# budicLED.net
KiCad netlist of a schematic drawn in EAGLE
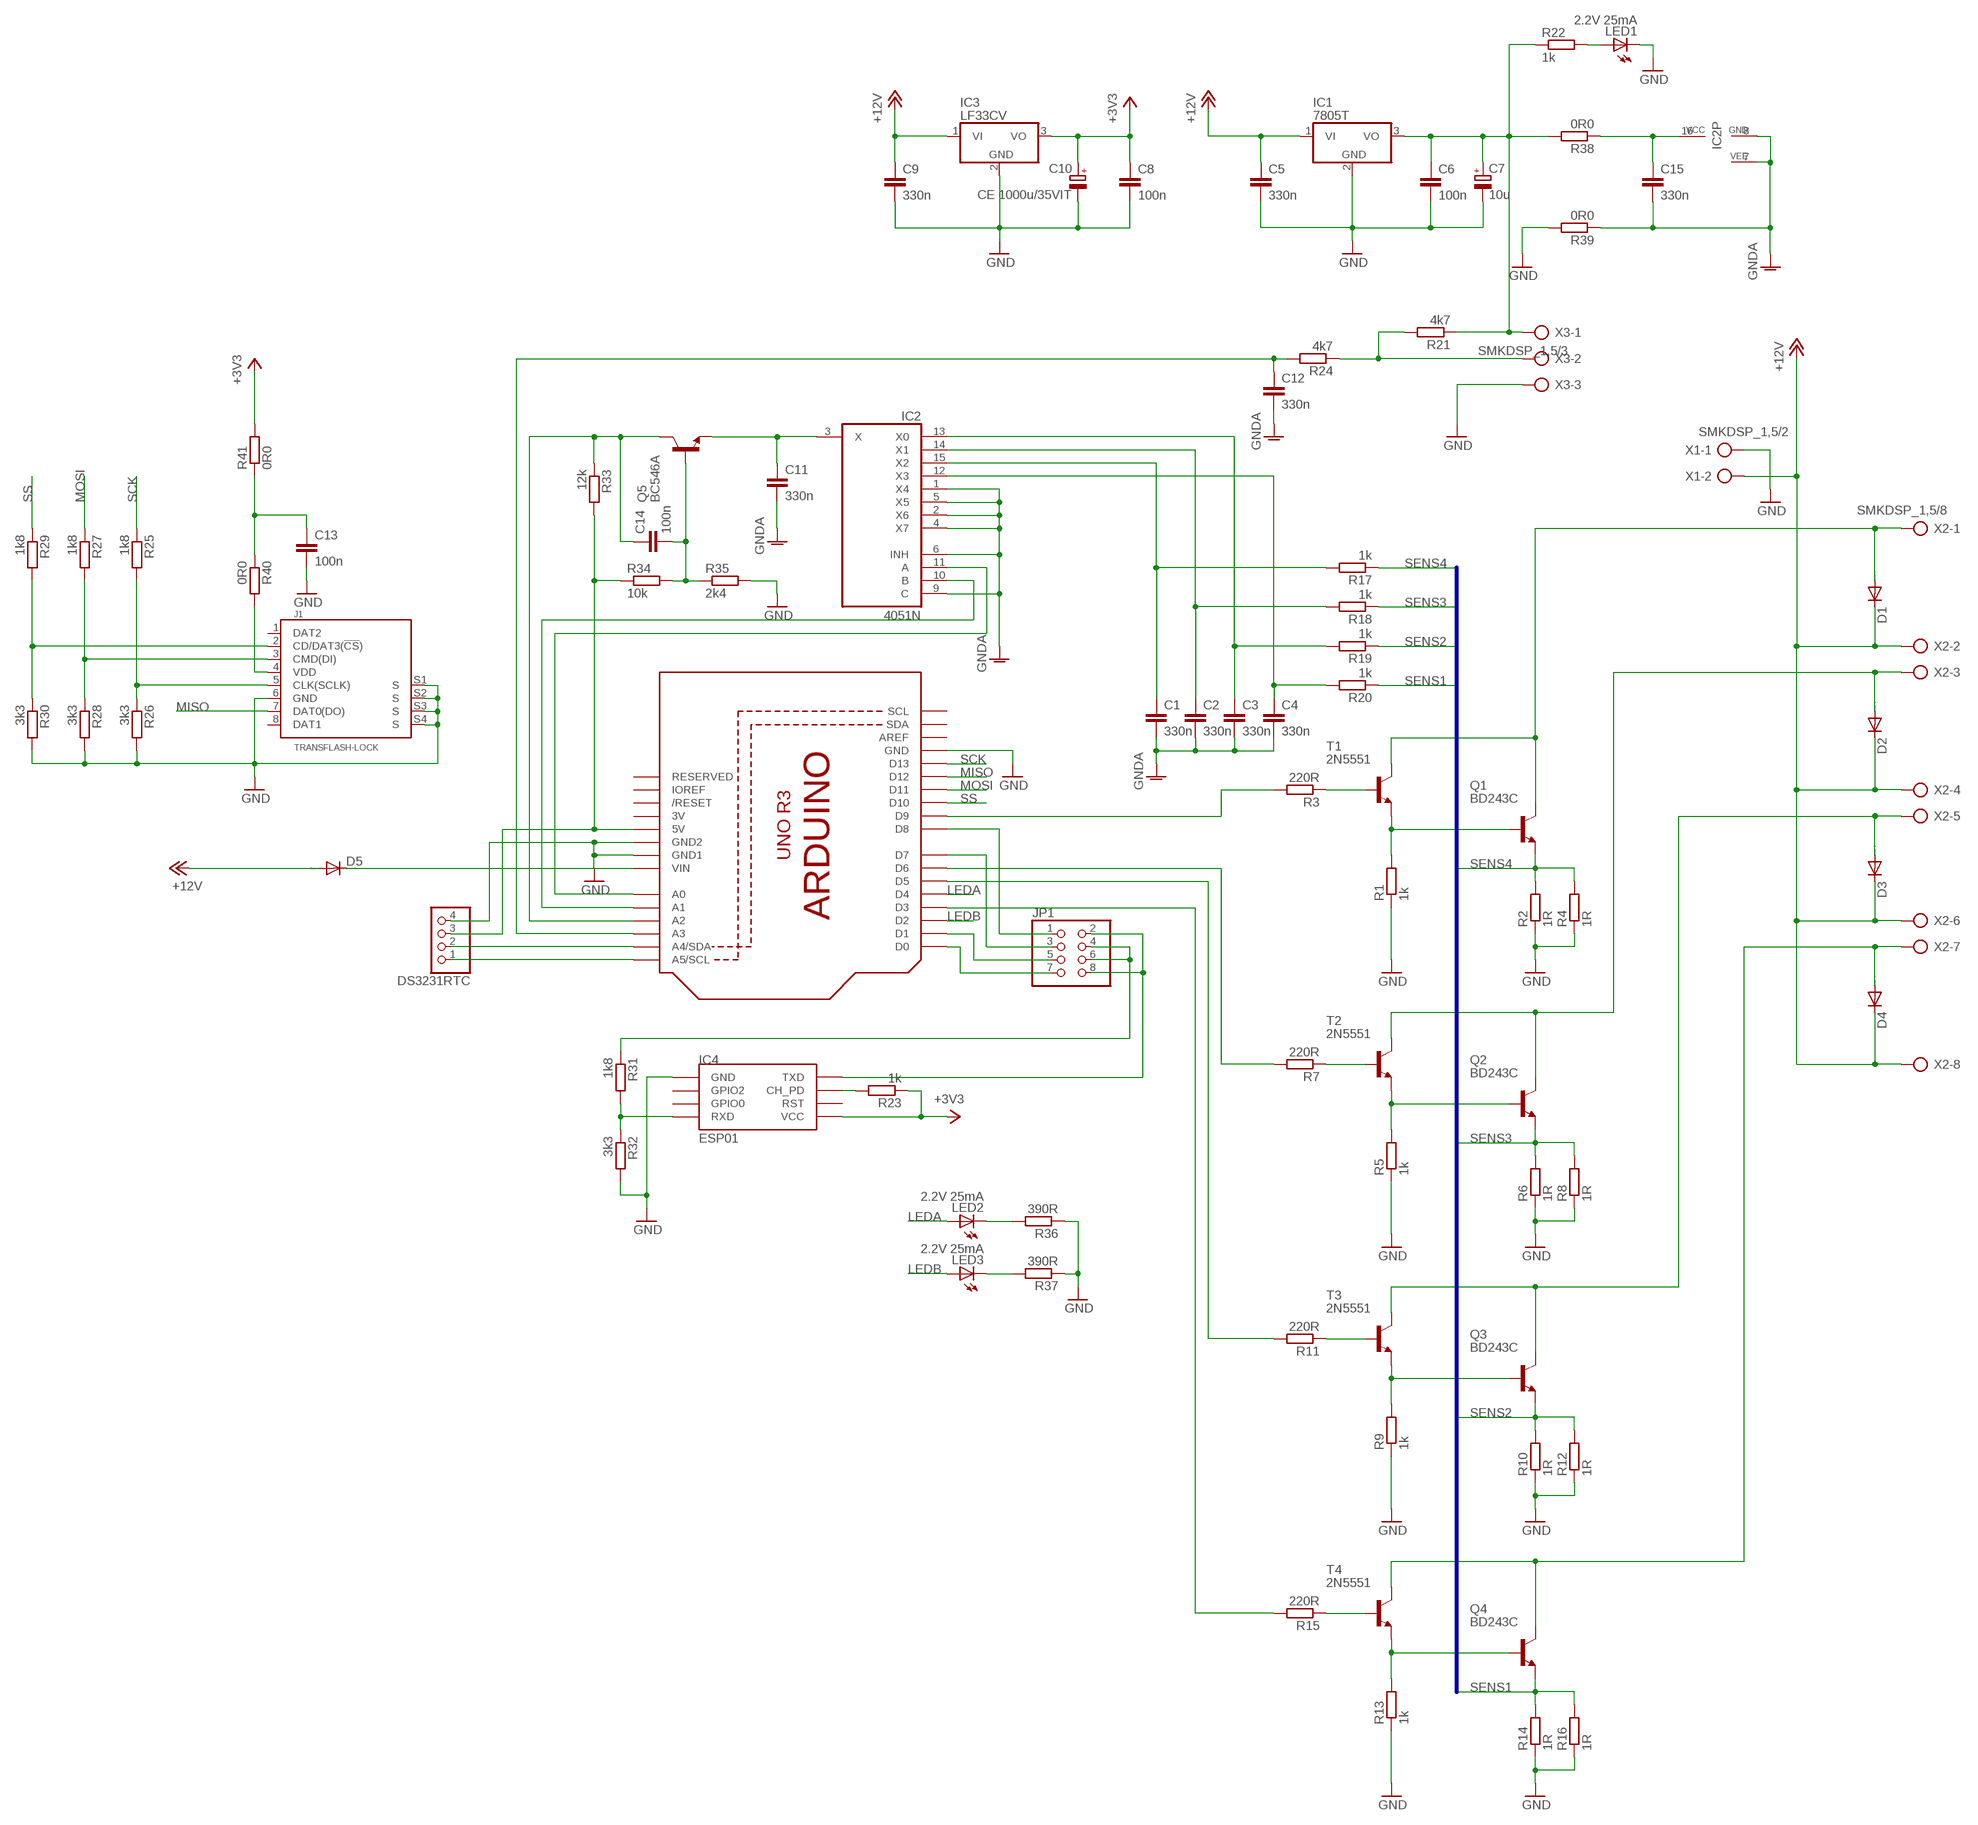
[diagram p0: schematic, sheet 1]

(export (version "E")
  (design (tool "Eeschema 10.0.6"))
  (components
    (comp (ref "C1")
      (value "330n")
      (footprint "eagle-import:C1206K")
      (libsource (lib "eagle-import") (part "C-EUC1206K"))
    )
    (comp (ref "C2")
      (value "330n")
      (footprint "eagle-import:C1206K")
      (libsource (lib "eagle-import") (part "C-EUC1206K"))
    )
    (comp (ref "C3")
      (value "330n")
      (footprint "eagle-import:C1206K")
      (libsource (lib "eagle-import") (part "C-EUC1206K"))
    )
    (comp (ref "C4")
      (value "330n")
      (footprint "eagle-import:C1206K")
      (libsource (lib "eagle-import") (part "C-EUC1206K"))
    )
    (comp (ref "C5")
      (value "330n")
      (footprint "eagle-import:C1206K")
      (libsource (lib "eagle-import") (part "C-EUC1206K"))
    )
    (comp (ref "C6")
      (value "100n")
      (footprint "eagle-import:C1206K")
      (libsource (lib "eagle-import") (part "C-EUC1206K"))
    )
    (comp (ref "C7")
      (value "10u")
      (footprint "eagle-import:E5-10,5")
      (libsource (lib "eagle-import") (part "CPOL-EUE5-10.5"))
    )
    (comp (ref "C8")
      (value "100n")
      (footprint "eagle-import:C1206K")
      (libsource (lib "eagle-import") (part "C-EUC1206K"))
    )
    (comp (ref "C9")
      (value "330n")
      (footprint "eagle-import:C1206K")
      (libsource (lib "eagle-import") (part "C-EUC1206K"))
    )
    (comp (ref "C10")
      (value "CE 1000u/35VIT")
      (footprint "eagle-import:E5-10,5")
      (libsource (lib "eagle-import") (part "CPOL-EUE5-10.5"))
    )
    (comp (ref "C11")
      (value "330n")
      (footprint "eagle-import:C1206K")
      (libsource (lib "eagle-import") (part "C-EUC1206K"))
    )
    (comp (ref "C12")
      (value "330n")
      (footprint "eagle-import:C1206K")
      (libsource (lib "eagle-import") (part "C-EUC1206K"))
    )
    (comp (ref "C13")
      (value "100n")
      (footprint "eagle-import:C1206K")
      (libsource (lib "eagle-import") (part "C-EUC1206K"))
    )
    (comp (ref "C14")
      (value "100n")
      (footprint "eagle-import:C1206K")
      (libsource (lib "eagle-import") (part "C-EUC1206K"))
    )
    (comp (ref "C15")
      (value "330n")
      (footprint "eagle-import:C1206K")
      (libsource (lib "eagle-import") (part "C-EUC1206K"))
    )
    (comp (ref "D1")
      (value "DIODE-DO201-15")
      (footprint "eagle-import:DO201-15")
      (libsource (lib "eagle-import") (part "DIODE-DO201-15"))
    )
    (comp (ref "D2")
      (value "DIODE-DO201-15")
      (footprint "eagle-import:DO201-15")
      (libsource (lib "eagle-import") (part "DIODE-DO201-15"))
    )
    (comp (ref "D3")
      (value "DIODE-DO201-15")
      (footprint "eagle-import:DO201-15")
      (libsource (lib "eagle-import") (part "DIODE-DO201-15"))
    )
    (comp (ref "D4")
      (value "DIODE-DO201-15")
      (footprint "eagle-import:DO201-15")
      (libsource (lib "eagle-import") (part "DIODE-DO201-15"))
    )
    (comp (ref "D5")
      (value "DIODE-MELF-MLL41")
      (footprint "eagle-import:MELF-MLL41")
      (libsource (lib "eagle-import") (part "DIODE-MELF-MLL41"))
    )
    (comp (ref "DS3231RTC")
      (value "PINHD-1X4")
      (footprint "eagle-import:1X04")
      (libsource (lib "eagle-import") (part "PINHD-1X4"))
    )
    (comp (ref "IC1")
      (value "7805T")
      (footprint "eagle-import:TO220H")
      (libsource (lib "eagle-import") (part "78T05"))
    )
    (comp (ref "IC2")
      (value "4051N")
      (footprint "eagle-import:DIL16")
      (libsource (lib "eagle-import") (part "4051N"))
    )
    (comp (ref "IC3")
      (value "LF33CV")
      (footprint "eagle-import:TO220H")
      (libsource (lib "eagle-import") (part "78T05"))
    )
    (comp (ref "IC4")
      (value "ESP01")
      (footprint "eagle-import:ESP01")
      (libsource (lib "eagle-import") (part "ESP01"))
    )
    (comp (ref "J1")
      (value "TRANSFLASH-LOCK")
      (footprint "eagle-import:TRANSFLASH-LOCK-SOCK")
      (libsource (lib "eagle-import") (part "TRANSFLASH-LOCK"))
    )
    (comp (ref "JP1")
      (value "PINHD-2X4")
      (footprint "eagle-import:2X04")
      (libsource (lib "eagle-import") (part "PINHD-2X4"))
    )
    (comp (ref "LED1")
      (value "2.2V 25mA")
      (footprint "eagle-import:LED3MM")
      (libsource (lib "eagle-import") (part "LED3MM"))
    )
    (comp (ref "LED2")
      (value "2.2V 25mA")
      (footprint "eagle-import:LED3MM")
      (libsource (lib "eagle-import") (part "LED3MM"))
    )
    (comp (ref "LED3")
      (value "2.2V 25mA")
      (footprint "eagle-import:LED3MM")
      (libsource (lib "eagle-import") (part "LED3MM"))
    )
    (comp (ref "Q1")
      (value "BD243C")
      (footprint "eagle-import:TO220")
      (libsource (lib "eagle-import") (part "-NPN-TO220"))
    )
    (comp (ref "Q2")
      (value "BD243C")
      (footprint "eagle-import:TO220")
      (libsource (lib "eagle-import") (part "-NPN-TO220"))
    )
    (comp (ref "Q3")
      (value "BD243C")
      (footprint "eagle-import:TO220")
      (libsource (lib "eagle-import") (part "-NPN-TO220"))
    )
    (comp (ref "Q4")
      (value "BD243C")
      (footprint "eagle-import:TO220")
      (libsource (lib "eagle-import") (part "-NPN-TO220"))
    )
    (comp (ref "Q5")
      (value "BC546A")
      (footprint "eagle-import:TO92-EBC")
      (libsource (lib "eagle-import") (part "BC546A"))
    )
    (comp (ref "R1")
      (value "1k")
      (footprint "eagle-import:0207_12")
      (libsource (lib "eagle-import") (part "R-EU_0207/12"))
    )
    (comp (ref "R2")
      (value "1R")
      (footprint "eagle-import:0411_15")
      (libsource (lib "eagle-import") (part "R-EU_0411/15"))
    )
    (comp (ref "R3")
      (value "220R")
      (footprint "eagle-import:0207_12")
      (libsource (lib "eagle-import") (part "R-EU_0207/12"))
    )
    (comp (ref "R4")
      (value "1R")
      (footprint "eagle-import:0411_15")
      (libsource (lib "eagle-import") (part "R-EU_0411/15"))
    )
    (comp (ref "R5")
      (value "1k")
      (footprint "eagle-import:0207_12")
      (libsource (lib "eagle-import") (part "R-EU_0207/12"))
    )
    (comp (ref "R6")
      (value "1R")
      (footprint "eagle-import:0411_15")
      (libsource (lib "eagle-import") (part "R-EU_0411/15"))
    )
    (comp (ref "R7")
      (value "220R")
      (footprint "eagle-import:0207_12")
      (libsource (lib "eagle-import") (part "R-EU_0207/12"))
    )
    (comp (ref "R8")
      (value "1R")
      (footprint "eagle-import:0411_15")
      (libsource (lib "eagle-import") (part "R-EU_0411/15"))
    )
    (comp (ref "R9")
      (value "1k")
      (footprint "eagle-import:0207_12")
      (libsource (lib "eagle-import") (part "R-EU_0207/12"))
    )
    (comp (ref "R10")
      (value "1R")
      (footprint "eagle-import:0411_15")
      (libsource (lib "eagle-import") (part "R-EU_0411/15"))
    )
    (comp (ref "R11")
      (value "220R")
      (footprint "eagle-import:0207_12")
      (libsource (lib "eagle-import") (part "R-EU_0207/12"))
    )
    (comp (ref "R12")
      (value "1R")
      (footprint "eagle-import:0411_15")
      (libsource (lib "eagle-import") (part "R-EU_0411/15"))
    )
    (comp (ref "R13")
      (value "1k")
      (footprint "eagle-import:0207_12")
      (libsource (lib "eagle-import") (part "R-EU_0207/12"))
    )
    (comp (ref "R14")
      (value "1R")
      (footprint "eagle-import:0411_15")
      (libsource (lib "eagle-import") (part "R-EU_0411/15"))
    )
    (comp (ref "R15")
      (value "220R")
      (footprint "eagle-import:0207_12")
      (libsource (lib "eagle-import") (part "R-EU_0207/12"))
    )
    (comp (ref "R16")
      (value "1R")
      (footprint "eagle-import:0411_15")
      (libsource (lib "eagle-import") (part "R-EU_0411/15"))
    )
    (comp (ref "R17")
      (value "1k")
      (footprint "eagle-import:R0805")
      (libsource (lib "eagle-import") (part "R-EU_R0805"))
    )
    (comp (ref "R18")
      (value "1k")
      (footprint "eagle-import:R0805")
      (libsource (lib "eagle-import") (part "R-EU_R0805"))
    )
    (comp (ref "R19")
      (value "1k")
      (footprint "eagle-import:R0805")
      (libsource (lib "eagle-import") (part "R-EU_R0805"))
    )
    (comp (ref "R20")
      (value "1k")
      (footprint "eagle-import:R0805")
      (libsource (lib "eagle-import") (part "R-EU_R0805"))
    )
    (comp (ref "R21")
      (value "4k7")
      (footprint "eagle-import:0207_12")
      (libsource (lib "eagle-import") (part "R-EU_0207/12"))
    )
    (comp (ref "R22")
      (value "1k")
      (footprint "eagle-import:R0805")
      (libsource (lib "eagle-import") (part "R-EU_R0805"))
    )
    (comp (ref "R23")
      (value "1k")
      (footprint "eagle-import:R0805")
      (libsource (lib "eagle-import") (part "R-EU_R0805"))
    )
    (comp (ref "R24")
      (value "4k7")
      (footprint "eagle-import:0207_15")
      (libsource (lib "eagle-import") (part "R-EU_0207/15"))
    )
    (comp (ref "R25")
      (value "1k8")
      (footprint "eagle-import:0207_12")
      (libsource (lib "eagle-import") (part "R-EU_0207/12"))
    )
    (comp (ref "R26")
      (value "3k3")
      (footprint "eagle-import:0207_12")
      (libsource (lib "eagle-import") (part "R-EU_0207/12"))
    )
    (comp (ref "R27")
      (value "1k8")
      (footprint "eagle-import:0207_12")
      (libsource (lib "eagle-import") (part "R-EU_0207/12"))
    )
    (comp (ref "R28")
      (value "3k3")
      (footprint "eagle-import:0207_12")
      (libsource (lib "eagle-import") (part "R-EU_0207/12"))
    )
    (comp (ref "R29")
      (value "1k8")
      (footprint "eagle-import:0207_12")
      (libsource (lib "eagle-import") (part "R-EU_0207/12"))
    )
    (comp (ref "R30")
      (value "3k3")
      (footprint "eagle-import:0207_12")
      (libsource (lib "eagle-import") (part "R-EU_0207/12"))
    )
    (comp (ref "R31")
      (value "1k8")
      (footprint "eagle-import:0207_12")
      (libsource (lib "eagle-import") (part "R-EU_0207/12"))
    )
    (comp (ref "R32")
      (value "3k3")
      (footprint "eagle-import:0207_12")
      (libsource (lib "eagle-import") (part "R-EU_0207/12"))
    )
    (comp (ref "R33")
      (value "12k")
      (footprint "eagle-import:0207_12")
      (libsource (lib "eagle-import") (part "R-EU_0207/12"))
    )
    (comp (ref "R34")
      (value "10k")
      (footprint "eagle-import:0207_12")
      (libsource (lib "eagle-import") (part "R-EU_0207/12"))
    )
    (comp (ref "R35")
      (value "2k4")
      (footprint "eagle-import:0207_12")
      (libsource (lib "eagle-import") (part "R-EU_0207/12"))
    )
    (comp (ref "R36")
      (value "390R")
      (footprint "eagle-import:0207_12")
      (libsource (lib "eagle-import") (part "R-EU_0207/12"))
    )
    (comp (ref "R37")
      (value "390R")
      (footprint "eagle-import:0207_12")
      (libsource (lib "eagle-import") (part "R-EU_0207/12"))
    )
    (comp (ref "R38")
      (value "0R0")
      (footprint "eagle-import:0207_15")
      (libsource (lib "eagle-import") (part "R-EU_0207/15"))
    )
    (comp (ref "R39")
      (value "0R0")
      (footprint "eagle-import:0207_12")
      (libsource (lib "eagle-import") (part "R-EU_0207/12"))
    )
    (comp (ref "R40")
      (value "0R0")
      (footprint "eagle-import:0207_12")
      (libsource (lib "eagle-import") (part "R-EU_0207/12"))
    )
    (comp (ref "R41")
      (value "0R0")
      (footprint "eagle-import:0207_12")
      (libsource (lib "eagle-import") (part "R-EU_0207/12"))
    )
    (comp (ref "T1")
      (value "2N5551")
      (footprint "eagle-import:TO92-CBE")
      (libsource (lib "eagle-import") (part "-NPN-TO92-CBE2N5551"))
    )
    (comp (ref "T2")
      (value "2N5551")
      (footprint "eagle-import:TO92-CBE")
      (libsource (lib "eagle-import") (part "-NPN-TO92-CBE2N5551"))
    )
    (comp (ref "T3")
      (value "2N5551")
      (footprint "eagle-import:TO92-CBE")
      (libsource (lib "eagle-import") (part "-NPN-TO92-CBE2N5551"))
    )
    (comp (ref "T4")
      (value "2N5551")
      (footprint "eagle-import:TO92-CBE")
      (libsource (lib "eagle-import") (part "-NPN-TO92-CBE2N5551"))
    )
    (comp (ref "U1")
      (value "ARDUINOR3-DIMENSION")
      (footprint "eagle-import:ARDUINOR3")
      (libsource (lib "eagle-import") (part "ARDUINOR3-DIMENSION"))
    )
    (comp (ref "X1")
      (value "SMKDSP_1,5/2")
      (footprint "eagle-import:SMKDSP_1,5_2")
      (fields (field (name "MF") "FARNELL") (field (name "MPN") "1733570"))
      (libsource (lib "eagle-import") (part "SMKDSP_1,5/2"))
    )
    (comp (ref "X2")
      (value "SMKDSP_1,5/8")
      (footprint "eagle-import:SMKDSP_1,5_8")
      (fields (field (name "MF") "FARNELL") (field (name "MPN") "1733635"))
      (libsource (lib "eagle-import") (part "SMKDSP_1,5/8"))
    )
    (comp (ref "X3")
      (value "SMKDSP_1,5/3")
      (footprint "eagle-import:SMKDSP_1,5_3")
      (fields (field (name "MF") "FARNELL") (field (name "MPN") "1733583"))
      (libsource (lib "eagle-import") (part "SMKDSP_1,5/3"))
    )
  )
  (nets
    (net (code "1") (name "+3V3") (class "Default")
      (node (ref "C10") (pin "+") (pinfunction "+_+") (pintype "passive"))
      (node (ref "C8") (pin "1") (pinfunction "1_1") (pintype "passive"))
      (node (ref "IC3") (pin "3") (pinfunction "VO_3") (pintype "passive"))
      (node (ref "IC4") (pin "VCC") (pinfunction "VCC_VCC") (pintype "bidirectional"))
      (node (ref "R23") (pin "1") (pinfunction "1_1") (pintype "passive"))
      (node (ref "R41") (pin "2") (pinfunction "2_2") (pintype "passive"))
    )
    (net (code "2") (name "+12V") (class "Default")
      (node (ref "C5") (pin "1") (pinfunction "1_1") (pintype "passive"))
      (node (ref "C9") (pin "1") (pinfunction "1_1") (pintype "passive"))
      (node (ref "D1") (pin "C") (pinfunction "C_C") (pintype "passive"))
      (node (ref "D2") (pin "C") (pinfunction "C_C") (pintype "passive"))
      (node (ref "D3") (pin "C") (pinfunction "C_C") (pintype "passive"))
      (node (ref "D4") (pin "C") (pinfunction "C_C") (pintype "passive"))
      (node (ref "D5") (pin "A") (pinfunction "A_A") (pintype "passive"))
      (node (ref "IC1") (pin "1") (pinfunction "VI_1") (pintype "input"))
      (node (ref "IC3") (pin "1") (pinfunction "VI_1") (pintype "input"))
      (node (ref "X1") (pin "2") (pinfunction "KL_2") (pintype "passive"))
      (node (ref "X2") (pin "2") (pinfunction "KL_2") (pintype "passive"))
      (node (ref "X2") (pin "4") (pinfunction "KL_4") (pintype "passive"))
      (node (ref "X2") (pin "6") (pinfunction "KL_6") (pintype "passive"))
      (node (ref "X2") (pin "8") (pinfunction "KL_8") (pintype "passive"))
    )
    (net (code "3") (name "/3V") (class "Default")
      (node (ref "U1") (pin "3V") (pinfunction "3V_3V") (pintype "power_in"))
    )
    (net (code "4") (name "/LEDA") (class "Default")
      (node (ref "LED2") (pin "A") (pinfunction "A_A") (pintype "passive"))
      (node (ref "U1") (pin "D4") (pinfunction "D4_D4") (pintype "bidirectional"))
    )
    (net (code "5") (name "/LEDB") (class "Default")
      (node (ref "LED3") (pin "A") (pinfunction "A_A") (pintype "passive"))
      (node (ref "U1") (pin "D2") (pinfunction "D2_D2") (pintype "bidirectional"))
    )
    (net (code "6") (name "/MISO") (class "Default")
      (node (ref "J1") (pin "7") (pinfunction "DAT0(DO)_7") (pintype "bidirectional"))
      (node (ref "U1") (pin "D12") (pinfunction "D12_D12") (pintype "bidirectional"))
    )
    (net (code "7") (name "/MOSI") (class "Default")
      (node (ref "R27") (pin "1") (pinfunction "1_1") (pintype "passive"))
      (node (ref "U1") (pin "D11") (pinfunction "D11_D11") (pintype "bidirectional"))
    )
    (net (code "8") (name "/SCK") (class "Default")
      (node (ref "R25") (pin "1") (pinfunction "1_1") (pintype "passive"))
      (node (ref "U1") (pin "D13") (pinfunction "D13_D13") (pintype "bidirectional"))
    )
    (net (code "9") (name "/SENS1") (class "Default")
      (node (ref "Q4") (pin "3") (pinfunction "E_3") (pintype "passive"))
      (node (ref "R14") (pin "2") (pinfunction "2_2") (pintype "passive"))
      (node (ref "R16") (pin "2") (pinfunction "2_2") (pintype "passive"))
      (node (ref "R20") (pin "1") (pinfunction "1_1") (pintype "passive"))
    )
    (net (code "10") (name "/SENS2") (class "Default")
      (node (ref "Q3") (pin "3") (pinfunction "E_3") (pintype "passive"))
      (node (ref "R10") (pin "2") (pinfunction "2_2") (pintype "passive"))
      (node (ref "R12") (pin "2") (pinfunction "2_2") (pintype "passive"))
      (node (ref "R19") (pin "1") (pinfunction "1_1") (pintype "passive"))
    )
    (net (code "11") (name "/SENS3") (class "Default")
      (node (ref "Q2") (pin "3") (pinfunction "E_3") (pintype "passive"))
      (node (ref "R18") (pin "1") (pinfunction "1_1") (pintype "passive"))
      (node (ref "R6") (pin "2") (pinfunction "2_2") (pintype "passive"))
      (node (ref "R8") (pin "2") (pinfunction "2_2") (pintype "passive"))
    )
    (net (code "12") (name "/SENS4") (class "Default")
      (node (ref "Q1") (pin "3") (pinfunction "E_3") (pintype "passive"))
      (node (ref "R17") (pin "1") (pinfunction "1_1") (pintype "passive"))
      (node (ref "R2") (pin "2") (pinfunction "2_2") (pintype "passive"))
      (node (ref "R4") (pin "2") (pinfunction "2_2") (pintype "passive"))
    )
    (net (code "13") (name "/SS") (class "Default")
      (node (ref "R29") (pin "1") (pinfunction "1_1") (pintype "passive"))
      (node (ref "U1") (pin "D10") (pinfunction "D10_D10") (pintype "bidirectional"))
    )
    (net (code "14") (name "GND") (class "Default")
      (node (ref "C10") (pin "-") (pinfunction "-_-") (pintype "passive"))
      (node (ref "C13") (pin "2") (pinfunction "2_2") (pintype "passive"))
      (node (ref "C5") (pin "2") (pinfunction "2_2") (pintype "passive"))
      (node (ref "C6") (pin "2") (pinfunction "2_2") (pintype "passive"))
      (node (ref "C7") (pin "-") (pinfunction "-_-") (pintype "passive"))
      (node (ref "C8") (pin "2") (pinfunction "2_2") (pintype "passive"))
      (node (ref "C9") (pin "2") (pinfunction "2_2") (pintype "passive"))
      (node (ref "DS3231RTC") (pin "4") (pinfunction "4_4") (pintype "passive"))
      (node (ref "IC1") (pin "2") (pinfunction "GND_2") (pintype "passive"))
      (node (ref "IC3") (pin "2") (pinfunction "GND_2") (pintype "passive"))
      (node (ref "IC4") (pin "GND") (pinfunction "GND_GND") (pintype "bidirectional"))
      (node (ref "J1") (pin "6") (pinfunction "GND_6") (pintype "power_in"))
      (node (ref "J1") (pin "S1") (pinfunction "S_S1") (pintype "passive"))
      (node (ref "J1") (pin "S2") (pinfunction "S_S2") (pintype "passive"))
      (node (ref "J1") (pin "S3") (pinfunction "S_S3") (pintype "passive"))
      (node (ref "J1") (pin "S4") (pinfunction "S_S4") (pintype "passive"))
      (node (ref "LED1") (pin "K") (pinfunction "C_K") (pintype "passive"))
      (node (ref "R1") (pin "1") (pinfunction "1_1") (pintype "passive"))
      (node (ref "R10") (pin "1") (pinfunction "1_1") (pintype "passive"))
      (node (ref "R12") (pin "1") (pinfunction "1_1") (pintype "passive"))
      (node (ref "R13") (pin "1") (pinfunction "1_1") (pintype "passive"))
      (node (ref "R14") (pin "1") (pinfunction "1_1") (pintype "passive"))
      (node (ref "R16") (pin "1") (pinfunction "1_1") (pintype "passive"))
      (node (ref "R2") (pin "1") (pinfunction "1_1") (pintype "passive"))
      (node (ref "R26") (pin "2") (pinfunction "2_2") (pintype "passive"))
      (node (ref "R28") (pin "2") (pinfunction "2_2") (pintype "passive"))
      (node (ref "R30") (pin "2") (pinfunction "2_2") (pintype "passive"))
      (node (ref "R32") (pin "2") (pinfunction "2_2") (pintype "passive"))
      (node (ref "R35") (pin "2") (pinfunction "2_2") (pintype "passive"))
      (node (ref "R36") (pin "1") (pinfunction "1_1") (pintype "passive"))
      (node (ref "R37") (pin "1") (pinfunction "1_1") (pintype "passive"))
      (node (ref "R39") (pin "2") (pinfunction "2_2") (pintype "passive"))
      (node (ref "R4") (pin "1") (pinfunction "1_1") (pintype "passive"))
      (node (ref "R5") (pin "1") (pinfunction "1_1") (pintype "passive"))
      (node (ref "R6") (pin "1") (pinfunction "1_1") (pintype "passive"))
      (node (ref "R8") (pin "1") (pinfunction "1_1") (pintype "passive"))
      (node (ref "R9") (pin "1") (pinfunction "1_1") (pintype "passive"))
      (node (ref "U1") (pin "GND") (pinfunction "GND_GND") (pintype "power_in"))
      (node (ref "U1") (pin "GND1") (pinfunction "GND1_GND1") (pintype "power_in"))
      (node (ref "U1") (pin "GND2") (pinfunction "GND2_GND2") (pintype "power_in"))
      (node (ref "X1") (pin "1") (pinfunction "KL_1") (pintype "passive"))
      (node (ref "X3") (pin "3") (pinfunction "KL_3") (pintype "passive"))
    )
    (net (code "15") (name "GNDA") (class "Default")
      (node (ref "C1") (pin "2") (pinfunction "2_2") (pintype "passive"))
      (node (ref "C11") (pin "2") (pinfunction "2_2") (pintype "passive"))
      (node (ref "C12") (pin "2") (pinfunction "2_2") (pintype "passive"))
      (node (ref "C15") (pin "2") (pinfunction "2_2") (pintype "passive"))
      (node (ref "C2") (pin "2") (pinfunction "2_2") (pintype "passive"))
      (node (ref "C3") (pin "2") (pinfunction "2_2") (pintype "passive"))
      (node (ref "C4") (pin "2") (pinfunction "2_2") (pintype "passive"))
      (node (ref "IC2") (pin "1") (pinfunction "X4_1") (pintype "bidirectional"))
      (node (ref "IC2") (pin "2") (pinfunction "X6_2") (pintype "bidirectional"))
      (node (ref "IC2") (pin "4") (pinfunction "X7_4") (pintype "bidirectional"))
      (node (ref "IC2") (pin "5") (pinfunction "X5_5") (pintype "bidirectional"))
      (node (ref "IC2") (pin "6") (pinfunction "INH_6") (pintype "input"))
      (node (ref "IC2") (pin "7") (pinfunction "VEE_7") (pintype "power_in"))
      (node (ref "IC2") (pin "8") (pinfunction "GND_8") (pintype "power_in"))
      (node (ref "IC2") (pin "9") (pinfunction "C_9") (pintype "input"))
      (node (ref "R39") (pin "1") (pinfunction "1_1") (pintype "passive"))
    )
    (net (code "16") (name "Net-(C12-Pad1)") (class "Default")
      (node (ref "C12") (pin "1") (pinfunction "1_1") (pintype "passive"))
      (node (ref "R24") (pin "2") (pinfunction "2_2") (pintype "passive"))
      (node (ref "U1") (pin "A3") (pinfunction "A3_A3") (pintype "bidirectional"))
    )
    (net (code "17") (name "Net-(C13-Pad1)") (class "Default")
      (node (ref "C13") (pin "1") (pinfunction "1_1") (pintype "passive"))
      (node (ref "R40") (pin "1") (pinfunction "1_1") (pintype "passive"))
      (node (ref "R41") (pin "1") (pinfunction "1_1") (pintype "passive"))
    )
    (net (code "18") (name "Net-(C14-Pad1)") (class "Default")
      (node (ref "C14") (pin "1") (pinfunction "1_1") (pintype "passive"))
      (node (ref "Q5") (pin "C") (pinfunction "C_C") (pintype "passive"))
      (node (ref "R33") (pin "1") (pinfunction "1_1") (pintype "passive"))
      (node (ref "U1") (pin "A2") (pinfunction "A2_A2") (pintype "bidirectional"))
    )
    (net (code "19") (name "Net-(C14-Pad2)") (class "Default")
      (node (ref "C14") (pin "2") (pinfunction "2_2") (pintype "passive"))
      (node (ref "Q5") (pin "B") (pinfunction "B_B") (pintype "passive"))
      (node (ref "R34") (pin "2") (pinfunction "2_2") (pintype "passive"))
      (node (ref "R35") (pin "1") (pinfunction "1_1") (pintype "passive"))
    )
    (net (code "20") (name "Net-(D5-PadC)") (class "Default")
      (node (ref "D5") (pin "C") (pinfunction "C_C") (pintype "passive"))
      (node (ref "U1") (pin "VIN") (pinfunction "VIN_VIN") (pintype "power_in"))
    )
    (net (code "21") (name "Net-(DS3231RTC-Pad3)") (class "Default")
      (node (ref "DS3231RTC") (pin "3") (pinfunction "3_3") (pintype "passive"))
      (node (ref "R33") (pin "2") (pinfunction "2_2") (pintype "passive"))
      (node (ref "R34") (pin "1") (pinfunction "1_1") (pintype "passive"))
      (node (ref "U1") (pin "5V") (pinfunction "5V_5V") (pintype "power_in"))
    )
    (net (code "22") (name "Net-(IC1-VO)") (class "Default")
      (node (ref "C6") (pin "1") (pinfunction "1_1") (pintype "passive"))
      (node (ref "C7") (pin "+") (pinfunction "+_+") (pintype "passive"))
      (node (ref "IC1") (pin "3") (pinfunction "VO_3") (pintype "passive"))
      (node (ref "R21") (pin "1") (pinfunction "1_1") (pintype "passive"))
      (node (ref "R22") (pin "1") (pinfunction "1_1") (pintype "passive"))
      (node (ref "R38") (pin "2") (pinfunction "2_2") (pintype "passive"))
      (node (ref "X3") (pin "1") (pinfunction "KL_1") (pintype "passive"))
    )
    (net (code "23") (name "Net-(IC2A-A)") (class "Default")
      (node (ref "IC2") (pin "11") (pinfunction "A_11") (pintype "input"))
      (node (ref "U1") (pin "A0") (pinfunction "A0_A0") (pintype "bidirectional"))
    )
    (net (code "24") (name "Net-(IC2A-B)") (class "Default")
      (node (ref "IC2") (pin "10") (pinfunction "B_10") (pintype "input"))
      (node (ref "U1") (pin "A1") (pinfunction "A1_A1") (pintype "bidirectional"))
    )
    (net (code "25") (name "Net-(IC2A-X)") (class "Default")
      (node (ref "C11") (pin "1") (pinfunction "1_1") (pintype "passive"))
      (node (ref "IC2") (pin "3") (pinfunction "X_3") (pintype "bidirectional"))
      (node (ref "Q5") (pin "E") (pinfunction "E_E") (pintype "passive"))
    )
    (net (code "26") (name "Net-(IC2A-X0)") (class "Default")
      (node (ref "C3") (pin "1") (pinfunction "1_1") (pintype "passive"))
      (node (ref "IC2") (pin "13") (pinfunction "X0_13") (pintype "bidirectional"))
      (node (ref "R19") (pin "2") (pinfunction "2_2") (pintype "passive"))
    )
    (net (code "27") (name "Net-(IC2A-X1)") (class "Default")
      (node (ref "C2") (pin "1") (pinfunction "1_1") (pintype "passive"))
      (node (ref "IC2") (pin "14") (pinfunction "X1_14") (pintype "bidirectional"))
      (node (ref "R18") (pin "2") (pinfunction "2_2") (pintype "passive"))
    )
    (net (code "28") (name "Net-(IC2A-X2)") (class "Default")
      (node (ref "C1") (pin "1") (pinfunction "1_1") (pintype "passive"))
      (node (ref "IC2") (pin "15") (pinfunction "X2_15") (pintype "bidirectional"))
      (node (ref "R17") (pin "2") (pinfunction "2_2") (pintype "passive"))
    )
    (net (code "29") (name "Net-(IC2A-X3)") (class "Default")
      (node (ref "C4") (pin "1") (pinfunction "1_1") (pintype "passive"))
      (node (ref "IC2") (pin "12") (pinfunction "X3_12") (pintype "bidirectional"))
      (node (ref "R20") (pin "2") (pinfunction "2_2") (pintype "passive"))
    )
    (net (code "30") (name "Net-(IC2B-VCC)") (class "Default")
      (node (ref "C15") (pin "1") (pinfunction "1_1") (pintype "passive"))
      (node (ref "IC2") (pin "16") (pinfunction "VCC_16") (pintype "power_in"))
      (node (ref "R38") (pin "1") (pinfunction "1_1") (pintype "passive"))
    )
    (net (code "31") (name "Net-(IC4-PadCH_PD)") (class "Default")
      (node (ref "IC4") (pin "CH_PD") (pinfunction "CH_PD_CH_PD") (pintype "bidirectional"))
      (node (ref "R23") (pin "2") (pinfunction "2_2") (pintype "passive"))
    )
    (net (code "32") (name "Net-(IC4-RXD)") (class "Default")
      (node (ref "IC4") (pin "RX") (pinfunction "RXD_RX") (pintype "bidirectional"))
      (node (ref "R31") (pin "2") (pinfunction "2_2") (pintype "passive"))
      (node (ref "R32") (pin "1") (pinfunction "1_1") (pintype "passive"))
    )
    (net (code "33") (name "Net-(IC4-TXD)") (class "Default")
      (node (ref "IC4") (pin "TX") (pinfunction "TXD_TX") (pintype "bidirectional"))
      (node (ref "JP1") (pin "2") (pinfunction "2_2") (pintype "passive"))
      (node (ref "JP1") (pin "8") (pinfunction "8_8") (pintype "passive"))
    )
    (net (code "34") (name "Net-(J1-CD{slash}DAT3(~{CS}))") (class "Default")
      (node (ref "J1") (pin "2") (pinfunction "CD/DAT3(~{CS})_2") (pintype "bidirectional"))
      (node (ref "R29") (pin "2") (pinfunction "2_2") (pintype "passive"))
      (node (ref "R30") (pin "1") (pinfunction "1_1") (pintype "passive"))
    )
    (net (code "35") (name "Net-(J1-CLK(SCLK))") (class "Default")
      (node (ref "J1") (pin "5") (pinfunction "CLK(SCLK)_5") (pintype "bidirectional"))
      (node (ref "R25") (pin "2") (pinfunction "2_2") (pintype "passive"))
      (node (ref "R26") (pin "1") (pinfunction "1_1") (pintype "passive"))
    )
    (net (code "36") (name "Net-(J1-CMD(DI))") (class "Default")
      (node (ref "J1") (pin "3") (pinfunction "CMD(DI)_3") (pintype "bidirectional"))
      (node (ref "R27") (pin "2") (pinfunction "2_2") (pintype "passive"))
      (node (ref "R28") (pin "1") (pinfunction "1_1") (pintype "passive"))
    )
    (net (code "37") (name "Net-(J1-VDD)") (class "Default")
      (node (ref "J1") (pin "4") (pinfunction "VDD_4") (pintype "power_in"))
      (node (ref "R40") (pin "2") (pinfunction "2_2") (pintype "passive"))
    )
    (net (code "38") (name "Net-(JP1-Pad1)") (class "Default")
      (node (ref "JP1") (pin "1") (pinfunction "1_1") (pintype "passive"))
      (node (ref "U1") (pin "D8") (pinfunction "D8_D8") (pintype "bidirectional"))
    )
    (net (code "39") (name "Net-(JP1-Pad3)") (class "Default")
      (node (ref "JP1") (pin "3") (pinfunction "3_3") (pintype "passive"))
      (node (ref "U1") (pin "D7") (pinfunction "D7_D7") (pintype "bidirectional"))
    )
    (net (code "40") (name "Net-(JP1-Pad4)") (class "Default")
      (node (ref "JP1") (pin "4") (pinfunction "4_4") (pintype "passive"))
      (node (ref "JP1") (pin "6") (pinfunction "6_6") (pintype "passive"))
      (node (ref "R31") (pin "1") (pinfunction "1_1") (pintype "passive"))
    )
    (net (code "41") (name "Net-(JP1-Pad5)") (class "Default")
      (node (ref "JP1") (pin "5") (pinfunction "5_5") (pintype "passive"))
      (node (ref "U1") (pin "D1") (pinfunction "D1_D1") (pintype "bidirectional"))
    )
    (net (code "42") (name "Net-(JP1-Pad7)") (class "Default")
      (node (ref "JP1") (pin "7") (pinfunction "7_7") (pintype "passive"))
      (node (ref "U1") (pin "D0") (pinfunction "D0_D0") (pintype "bidirectional"))
    )
    (net (code "43") (name "Net-(LED1-PadA)") (class "Default")
      (node (ref "LED1") (pin "A") (pinfunction "A_A") (pintype "passive"))
      (node (ref "R22") (pin "2") (pinfunction "2_2") (pintype "passive"))
    )
    (net (code "44") (name "Net-(LED2-C)") (class "Default")
      (node (ref "LED2") (pin "K") (pinfunction "C_K") (pintype "passive"))
      (node (ref "R36") (pin "2") (pinfunction "2_2") (pintype "passive"))
    )
    (net (code "45") (name "Net-(LED3-C)") (class "Default")
      (node (ref "LED3") (pin "K") (pinfunction "C_K") (pintype "passive"))
      (node (ref "R37") (pin "2") (pinfunction "2_2") (pintype "passive"))
    )
    (net (code "46") (name "Net-(Q1-B)") (class "Default")
      (node (ref "Q1") (pin "1") (pinfunction "B_1") (pintype "passive"))
      (node (ref "R1") (pin "2") (pinfunction "2_2") (pintype "passive"))
      (node (ref "T1") (pin "E") (pinfunction "E_E") (pintype "passive"))
    )
    (net (code "47") (name "Net-(Q1-C)") (class "Default")
      (node (ref "D1") (pin "A") (pinfunction "A_A") (pintype "passive"))
      (node (ref "Q1") (pin "2") (pinfunction "C_2") (pintype "passive"))
      (node (ref "T1") (pin "C") (pinfunction "C_C") (pintype "passive"))
      (node (ref "X2") (pin "1") (pinfunction "KL_1") (pintype "passive"))
    )
    (net (code "48") (name "Net-(Q2-B)") (class "Default")
      (node (ref "Q2") (pin "1") (pinfunction "B_1") (pintype "passive"))
      (node (ref "R5") (pin "2") (pinfunction "2_2") (pintype "passive"))
      (node (ref "T2") (pin "E") (pinfunction "E_E") (pintype "passive"))
    )
    (net (code "49") (name "Net-(Q2-C)") (class "Default")
      (node (ref "D2") (pin "A") (pinfunction "A_A") (pintype "passive"))
      (node (ref "Q2") (pin "2") (pinfunction "C_2") (pintype "passive"))
      (node (ref "T2") (pin "C") (pinfunction "C_C") (pintype "passive"))
      (node (ref "X2") (pin "3") (pinfunction "KL_3") (pintype "passive"))
    )
    (net (code "50") (name "Net-(Q3-B)") (class "Default")
      (node (ref "Q3") (pin "1") (pinfunction "B_1") (pintype "passive"))
      (node (ref "R9") (pin "2") (pinfunction "2_2") (pintype "passive"))
      (node (ref "T3") (pin "E") (pinfunction "E_E") (pintype "passive"))
    )
    (net (code "51") (name "Net-(Q3-C)") (class "Default")
      (node (ref "D3") (pin "A") (pinfunction "A_A") (pintype "passive"))
      (node (ref "Q3") (pin "2") (pinfunction "C_2") (pintype "passive"))
      (node (ref "T3") (pin "C") (pinfunction "C_C") (pintype "passive"))
      (node (ref "X2") (pin "5") (pinfunction "KL_5") (pintype "passive"))
    )
    (net (code "52") (name "Net-(Q4-B)") (class "Default")
      (node (ref "Q4") (pin "1") (pinfunction "B_1") (pintype "passive"))
      (node (ref "R13") (pin "2") (pinfunction "2_2") (pintype "passive"))
      (node (ref "T4") (pin "E") (pinfunction "E_E") (pintype "passive"))
    )
    (net (code "53") (name "Net-(Q4-C)") (class "Default")
      (node (ref "D4") (pin "A") (pinfunction "A_A") (pintype "passive"))
      (node (ref "Q4") (pin "2") (pinfunction "C_2") (pintype "passive"))
      (node (ref "T4") (pin "C") (pinfunction "C_C") (pintype "passive"))
      (node (ref "X2") (pin "7") (pinfunction "KL_7") (pintype "passive"))
    )
    (net (code "54") (name "Net-(R3-Pad1)") (class "Default")
      (node (ref "R3") (pin "1") (pinfunction "1_1") (pintype "passive"))
      (node (ref "T1") (pin "B") (pinfunction "B_B") (pintype "passive"))
    )
    (net (code "55") (name "Net-(R3-Pad2)") (class "Default")
      (node (ref "R3") (pin "2") (pinfunction "2_2") (pintype "passive"))
      (node (ref "U1") (pin "D9") (pinfunction "D9_D9") (pintype "bidirectional"))
    )
    (net (code "56") (name "Net-(R7-Pad1)") (class "Default")
      (node (ref "R7") (pin "1") (pinfunction "1_1") (pintype "passive"))
      (node (ref "T2") (pin "B") (pinfunction "B_B") (pintype "passive"))
    )
    (net (code "57") (name "Net-(R7-Pad2)") (class "Default")
      (node (ref "R7") (pin "2") (pinfunction "2_2") (pintype "passive"))
      (node (ref "U1") (pin "D6") (pinfunction "D6_D6") (pintype "bidirectional"))
    )
    (net (code "58") (name "Net-(R11-Pad1)") (class "Default")
      (node (ref "R11") (pin "1") (pinfunction "1_1") (pintype "passive"))
      (node (ref "T3") (pin "B") (pinfunction "B_B") (pintype "passive"))
    )
    (net (code "59") (name "Net-(R11-Pad2)") (class "Default")
      (node (ref "R11") (pin "2") (pinfunction "2_2") (pintype "passive"))
      (node (ref "U1") (pin "D5") (pinfunction "D5_D5") (pintype "bidirectional"))
    )
    (net (code "60") (name "Net-(R15-Pad1)") (class "Default")
      (node (ref "R15") (pin "1") (pinfunction "1_1") (pintype "passive"))
      (node (ref "T4") (pin "B") (pinfunction "B_B") (pintype "passive"))
    )
    (net (code "61") (name "Net-(R15-Pad2)") (class "Default")
      (node (ref "R15") (pin "2") (pinfunction "2_2") (pintype "passive"))
      (node (ref "U1") (pin "D3") (pinfunction "D3_D3") (pintype "bidirectional"))
    )
    (net (code "62") (name "Net-(U1-A4{slash}SDA)") (class "Default")
      (node (ref "DS3231RTC") (pin "2") (pinfunction "2_2") (pintype "passive"))
      (node (ref "U1") (pin "A4") (pinfunction "A4/SDA_A4") (pintype "bidirectional"))
    )
    (net (code "63") (name "Net-(U1-A5{slash}SCL)") (class "Default")
      (node (ref "DS3231RTC") (pin "1") (pinfunction "1_1") (pintype "passive"))
      (node (ref "U1") (pin "A5") (pinfunction "A5/SCL_A5") (pintype "bidirectional"))
    )
    (net (code "64") (name "Net-(X3B-KL)") (class "Default")
      (node (ref "R21") (pin "2") (pinfunction "2_2") (pintype "passive"))
      (node (ref "R24") (pin "1") (pinfunction "1_1") (pintype "passive"))
      (node (ref "X3") (pin "2") (pinfunction "KL_2") (pintype "passive"))
    )
    (net (code "65") (name "unconnected-(IC4-PadGPIO0)") (class "Default")
      (node (ref "IC4") (pin "GPIO0") (pinfunction "GPIO0_GPIO0") (pintype "bidirectional"))
    )
    (net (code "66") (name "unconnected-(IC4-PadGPIO2)") (class "Default")
      (node (ref "IC4") (pin "GPIO2") (pinfunction "GPIO2_GPIO2") (pintype "bidirectional"))
    )
    (net (code "67") (name "unconnected-(IC4-PadRST)") (class "Default")
      (node (ref "IC4") (pin "RST") (pinfunction "RST_RST") (pintype "bidirectional"))
    )
    (net (code "68") (name "unconnected-(J1-DAT1-Pad8)") (class "Default")
      (node (ref "J1") (pin "8") (pinfunction "DAT1_8") (pintype "bidirectional"))
    )
    (net (code "69") (name "unconnected-(J1-DAT2-Pad1)") (class "Default")
      (node (ref "J1") (pin "1") (pinfunction "DAT2_1") (pintype "bidirectional"))
    )
    (net (code "70") (name "unconnected-(U1-PadAREF)") (class "Default")
      (node (ref "U1") (pin "AREF") (pinfunction "AREF_AREF") (pintype "bidirectional"))
    )
    (net (code "71") (name "unconnected-(U1-PadIOREF)") (class "Default")
      (node (ref "U1") (pin "IOREF") (pinfunction "IOREF_IOREF") (pintype "output"))
    )
    (net (code "72") (name "unconnected-(U1-PadRESERVED)") (class "Default")
      (node (ref "U1") (pin "RESERVED") (pinfunction "RESERVED_RESERVED") (pintype "no_connect"))
    )
    (net (code "73") (name "unconnected-(U1-PadSCL)") (class "Default")
      (node (ref "U1") (pin "SCL") (pinfunction "SCL_SCL") (pintype "bidirectional"))
    )
    (net (code "74") (name "unconnected-(U1-PadSDA)") (class "Default")
      (node (ref "U1") (pin "SDA") (pinfunction "SDA_SDA") (pintype "bidirectional"))
    )
    (net (code "75") (name "unconnected-(U1-{slash}RESET-PadRESET)") (class "Default")
      (node (ref "U1") (pin "RESET") (pinfunction "/RESET_RESET") (pintype "bidirectional"))
    )
  )
)
